# RIGHT_AR0234.net
KiCad netlist of a schematic drawn in Altium Designer
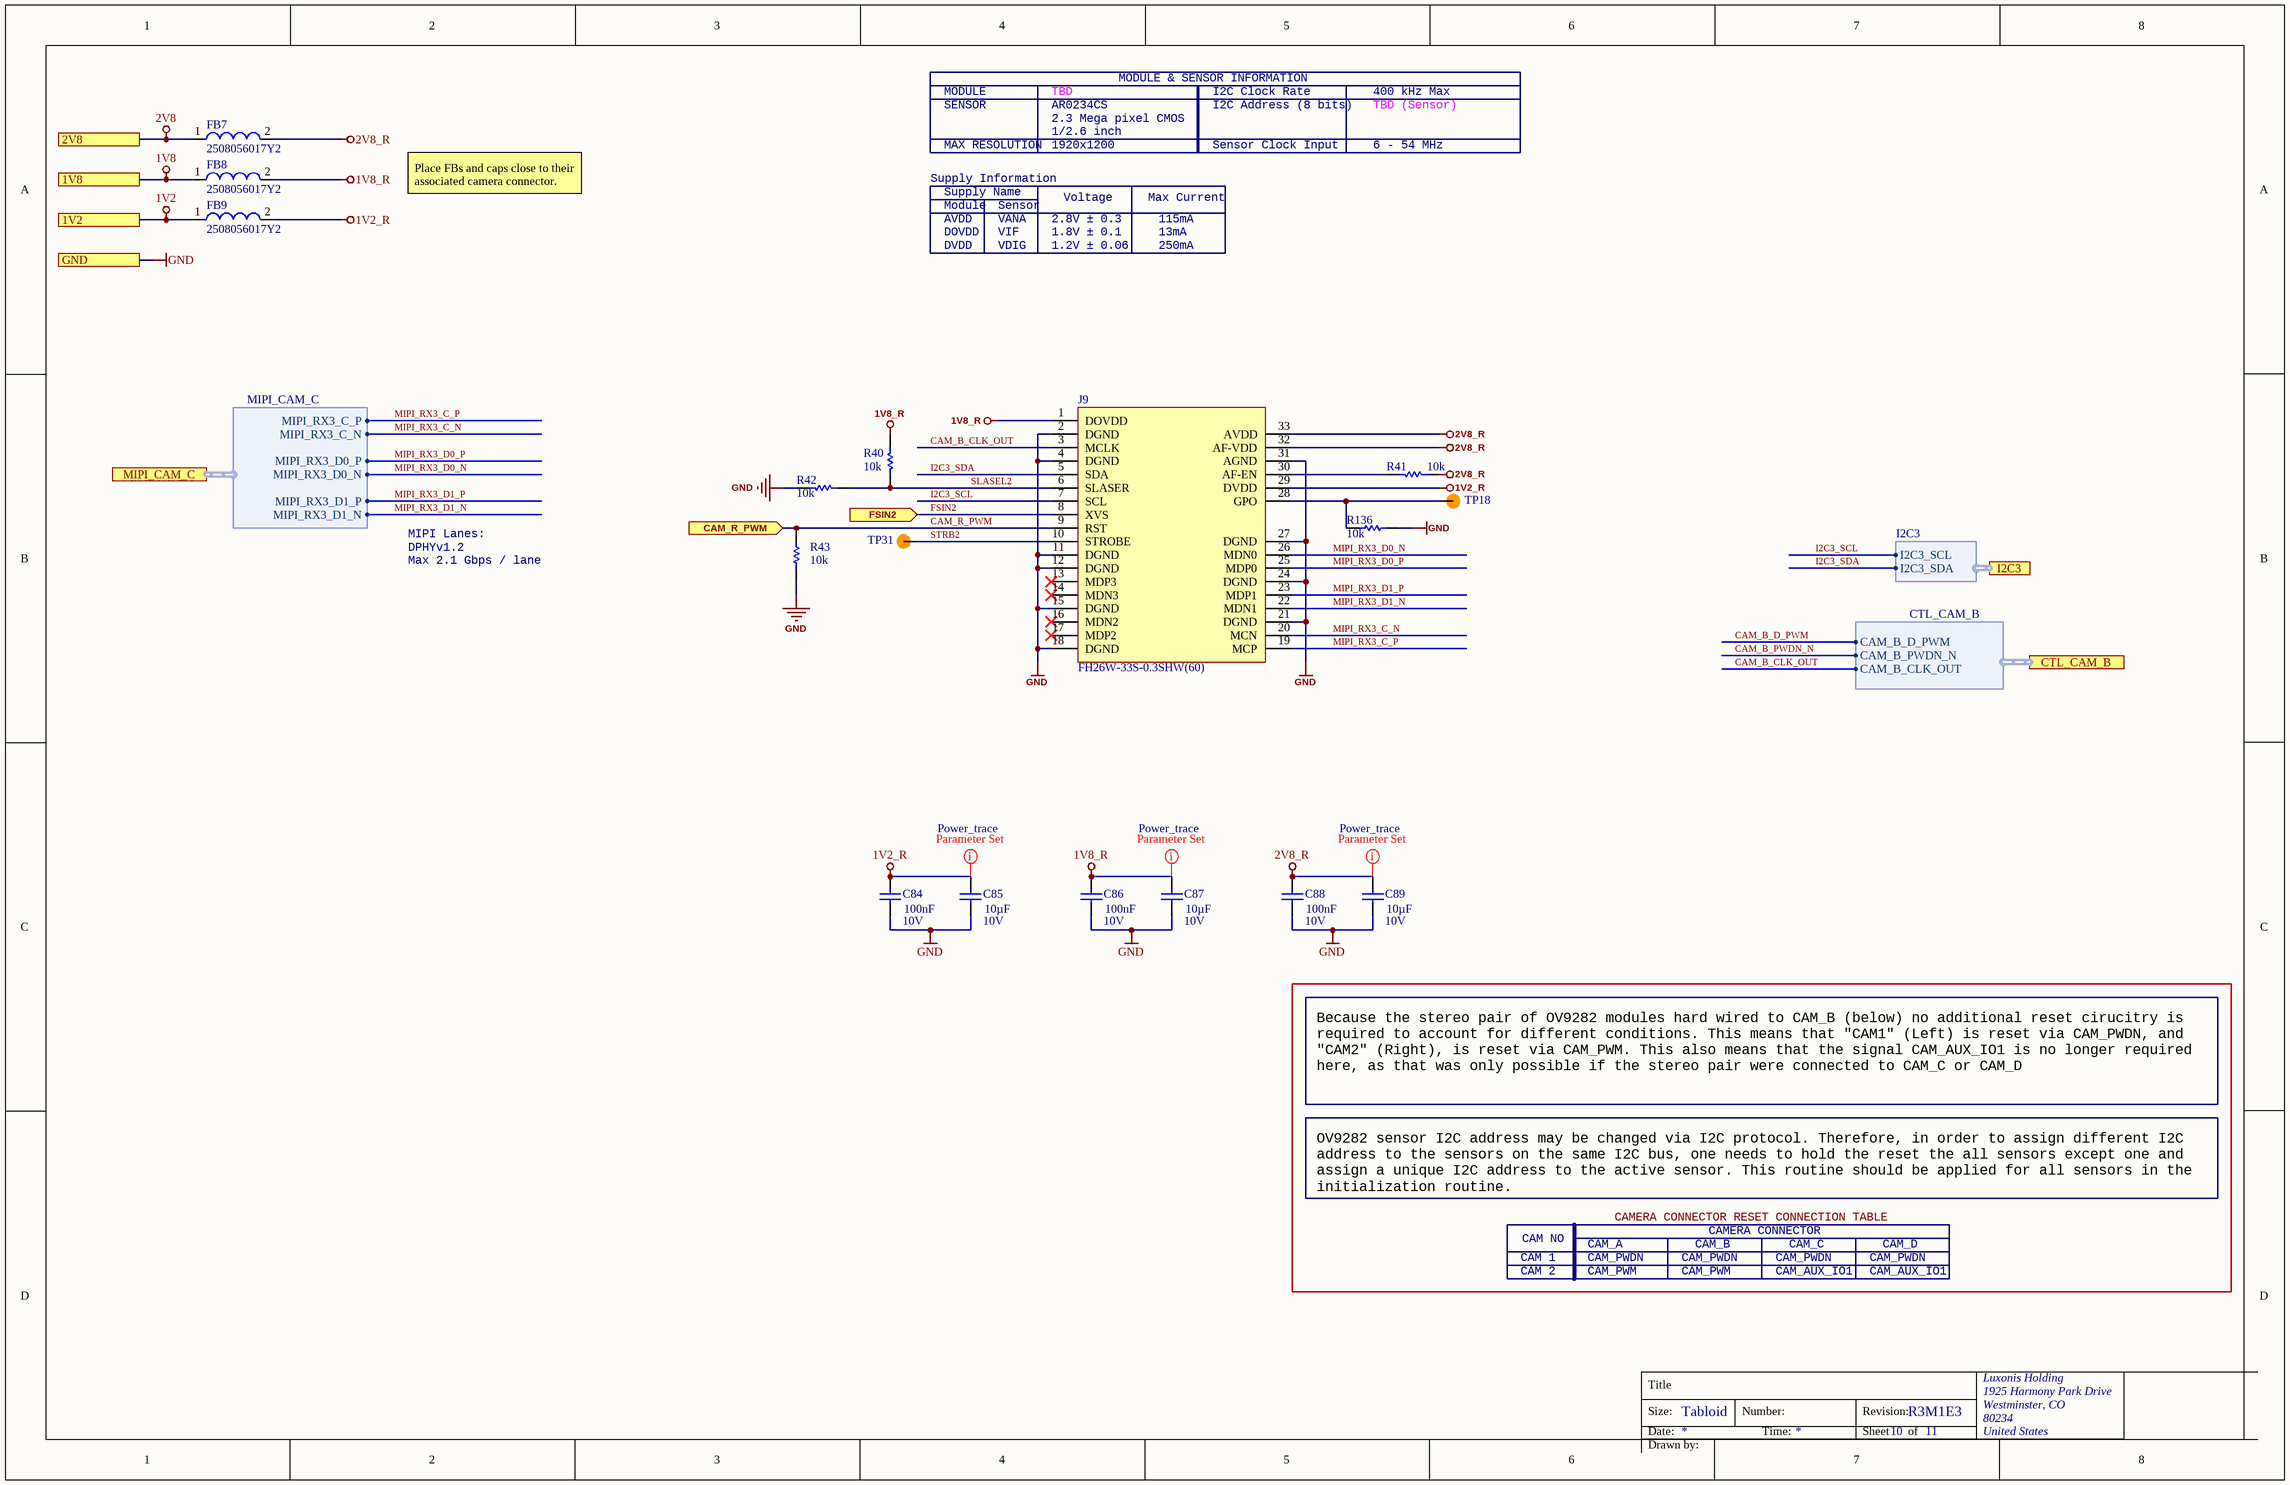
[diagram p0: RIGHT_AR0234.SchDoc]

(export (version "E")
  (design (tool "Eeschema 10.0.6"))
  (components
    (comp (ref "C84")
      (value "100nF")
      (footprint "CAPC0402(1005)70_L")
      (description "CAP CER 0.1UF 10V X7R 0402 5%")
      (fields
        (field (name "TOLERANCE") "5%")
        (field (name "VOLTAGE RATING") "10V")
        (field (name "Comment") "GRM155R71A104JA01D")
      )
      (libsource (lib "Luxonis LLC") (part "GRM188R61C475KAAJD"))
    )
    (comp (ref "C85")
      (value "10µF")
      (footprint "CAPC0603(1608)100_L")
      (description "CAP CER 10UF 10V X5R 0603 20%")
      (fields
        (field (name "TOLERANCE") "20%")
        (field (name "VOLTAGE RATING") "10V")
        (field (name "Comment") "GRM188R61A106ME69D")
      )
      (libsource (lib "Luxonis LLC") (part "LLL153C70G474ME17E"))
    )
    (comp (ref "C86")
      (value "100nF")
      (footprint "CAPC0402(1005)70_L")
      (description "CAP CER 0.1UF 10V X7R 0402 5%")
      (fields
        (field (name "TOLERANCE") "5%")
        (field (name "VOLTAGE RATING") "10V")
        (field (name "Comment") "GRM155R71A104JA01D")
      )
      (libsource (lib "Luxonis LLC") (part "GRM188R61C475KAAJD"))
    )
    (comp (ref "C87")
      (value "10µF")
      (footprint "CAPC0603(1608)100_L")
      (description "CAP CER 10UF 10V X5R 0603 20%")
      (fields
        (field (name "TOLERANCE") "20%")
        (field (name "VOLTAGE RATING") "10V")
        (field (name "Comment") "GRM188R61A106ME69D")
      )
      (libsource (lib "Luxonis LLC") (part "LLL153C70G474ME17E"))
    )
    (comp (ref "C88")
      (value "100nF")
      (footprint "CAPC0402(1005)70_L")
      (description "CAP CER 0.1UF 10V X7R 0402 5%")
      (fields
        (field (name "TOLERANCE") "5%")
        (field (name "VOLTAGE RATING") "10V")
        (field (name "Comment") "GRM155R71A104JA01D")
      )
      (libsource (lib "Luxonis LLC") (part "GRM188R61C475KAAJD"))
    )
    (comp (ref "C89")
      (value "10µF")
      (footprint "CAPC0603(1608)100_L")
      (description "CAP CER 10UF 10V X5R 0603 20%")
      (fields
        (field (name "TOLERANCE") "20%")
        (field (name "VOLTAGE RATING") "10V")
        (field (name "Comment") "GRM188R61A106ME69D")
      )
      (libsource (lib "Luxonis LLC") (part "LLL153C70G474ME17E"))
    )
    (comp (ref "FB7")
      (value "2508056017Y2")
      (footprint "2508056017Y2")
      (description "FERRITE BEAD, 0.1OHM, 2A, 0805, 600R/100MHz")
      (fields (field (name "TOLERANCE") "25%"))
      (libsource (lib "Luxonis LLC") (part "2508056017Y2"))
    )
    (comp (ref "FB8")
      (value "2508056017Y2")
      (footprint "2508056017Y2")
      (description "FERRITE BEAD, 0.1OHM, 2A, 0805, 600R/100MHz")
      (fields (field (name "TOLERANCE") "25%"))
      (libsource (lib "Luxonis LLC") (part "2508056017Y2"))
    )
    (comp (ref "FB9")
      (value "2508056017Y2")
      (footprint "2508056017Y2")
      (description "FERRITE BEAD, 0.1OHM, 2A, 0805, 600R/100MHz")
      (fields (field (name "TOLERANCE") "25%"))
      (libsource (lib "Luxonis LLC") (part "2508056017Y2"))
    )
    (comp (ref "J9")
      (value "FH26W-33S-0.3SHW(60)")
      (footprint "FH26W-33S-0.3SHW(60)")
      (description "FFC/FPC Connector, 33 Contact(s), 1 Row(s), Female, Right Angle, Surface Mount Terminal")
      (libsource (lib "Luxonis LLC") (part "FH26W-33S-0.3SHW(60)"))
    )
    (comp (ref "R40")
      (value "10k")
      (footprint "RESC0402(1005)_L")
      (description "RES SMD 10K OHM 1% 1/16W 0402")
      (fields (field (name "TOLERANCE") "1%") (field (name "Comment") "RC0402FR-1310KL"))
      (libsource (lib "Luxonis LLC") (part "RC0402FR-0722RL_1"))
    )
    (comp (ref "R41")
      (value "10k")
      (footprint "RESC0402(1005)_L")
      (description "RES SMD 10K OHM 1% 1/16W 0402")
      (fields (field (name "TOLERANCE") "1%") (field (name "Comment") "RC0402FR-1310KL"))
      (libsource (lib "Luxonis LLC") (part "RC0402FR-0722RL_1"))
    )
    (comp (ref "R42")
      (value "10k")
      (footprint "RESC0402(1005)_L")
      (description "RES SMD 10K OHM 1% 1/16W 0402")
      (fields (field (name "TOLERANCE") "1%") (field (name "Comment") "RC0402FR-1310KL"))
      (libsource (lib "Luxonis LLC") (part "RC0402FR-0722RL_1"))
    )
    (comp (ref "R43")
      (value "10k")
      (footprint "RESC0402(1005)_L")
      (description "RES SMD 10K OHM 1% 1/16W 0402")
      (fields (field (name "TOLERANCE") "1%") (field (name "Comment") "RC0402FR-1310KL"))
      (libsource (lib "Luxonis LLC") (part "RC0402FR-0722RL_1"))
    )
    (comp (ref "R136")
      (value "10k")
      (footprint "RESC0402(1005)_L")
      (description "RES SMD 10K OHM 1% 1/16W 0402")
      (fields (field (name "TOLERANCE") "1%") (field (name "Comment") "RC0402FR-1310KL"))
      (libsource (lib "Luxonis LLC") (part "RC0402FR-0722RL_1"))
    )
    (comp (ref "TP18")
      (value "TEST_POINT")
      (footprint "TP100_200_NS")
      (libsource (lib "Luxonis LLC") (part "TEST_POINT"))
    )
    (comp (ref "TP31")
      (value "TEST_POINT")
      (footprint "TP100_200_NS")
      (libsource (lib "Luxonis LLC") (part "TEST_POINT"))
    )
  )
  (nets
    (net (code "4") (name "/CAM_B_CLK_OUT") (class "Default")
      (node (ref "J9") (pin "3") (pinfunction "MCLK_3") (pintype "passive"))
    )
    (net (code "7") (name "/CAM_R_PWM") (class "Default")
      (node (ref "J9") (pin "9") (pinfunction "RST_9") (pintype "passive"))
      (node (ref "R43") (pin "2") (pinfunction "2_2") (pintype "passive"))
    )
    (net (code "8") (name "/FSIN2") (class "Default")
      (node (ref "J9") (pin "8") (pinfunction "XVS_8") (pintype "passive"))
    )
    (net (code "9") (name "/I2C3_SCL") (class "Default")
      (node (ref "J9") (pin "7") (pinfunction "SCL_7") (pintype "passive"))
    )
    (net (code "10") (name "/I2C3_SDA") (class "Default")
      (node (ref "J9") (pin "5") (pinfunction "SDA_5") (pintype "passive"))
    )
    (net (code "11") (name "/MIPI_RX3_C_N") (class "Default")
      (node (ref "J9") (pin "20") (pinfunction "MCN_20") (pintype "passive"))
    )
    (net (code "12") (name "/MIPI_RX3_C_P") (class "Default")
      (node (ref "J9") (pin "19") (pinfunction "MCP_19") (pintype "passive"))
    )
    (net (code "13") (name "/MIPI_RX3_D0_N") (class "Default")
      (node (ref "J9") (pin "26") (pinfunction "MDN0_26") (pintype "passive"))
    )
    (net (code "14") (name "/MIPI_RX3_D0_P") (class "Default")
      (node (ref "J9") (pin "25") (pinfunction "MDP0_25") (pintype "passive"))
    )
    (net (code "15") (name "/MIPI_RX3_D1_N") (class "Default")
      (node (ref "J9") (pin "22") (pinfunction "MDN1_22") (pintype "passive"))
    )
    (net (code "16") (name "/MIPI_RX3_D1_P") (class "Default")
      (node (ref "J9") (pin "23") (pinfunction "MDP1_23") (pintype "passive"))
    )
    (net (code "17") (name "/SLASEL2") (class "Default")
      (node (ref "J9") (pin "6") (pinfunction "SLASER_6") (pintype "passive"))
      (node (ref "R40") (pin "2") (pinfunction "2_2") (pintype "passive"))
      (node (ref "R42") (pin "2") (pinfunction "2_2") (pintype "passive"))
    )
    (net (code "18") (name "/STRB2") (class "Default")
      (node (ref "J9") (pin "10") (pinfunction "STROBE_10") (pintype "passive"))
      (node (ref "TP31") (pin "1") (pintype "passive"))
    )
    (net (code "22") (name "1V2") (class "Default")
      (node (ref "FB9") (pin "1") (pinfunction "1_1") (pintype "passive"))
    )
    (net (code "23") (name "1V2_R") (class "Default")
      (node (ref "C84") (pin "2") (pinfunction "2_2") (pintype "passive"))
      (node (ref "C85") (pin "2") (pinfunction "2_2") (pintype "passive"))
      (node (ref "FB9") (pin "2") (pinfunction "2_2") (pintype "passive"))
      (node (ref "J9") (pin "29") (pinfunction "DVDD_29") (pintype "passive"))
    )
    (net (code "24") (name "1V8") (class "Default")
      (node (ref "FB8") (pin "1") (pinfunction "1_1") (pintype "passive"))
    )
    (net (code "25") (name "1V8_R") (class "Default")
      (node (ref "C86") (pin "2") (pinfunction "2_2") (pintype "passive"))
      (node (ref "C87") (pin "2") (pinfunction "2_2") (pintype "passive"))
      (node (ref "FB8") (pin "2") (pinfunction "2_2") (pintype "passive"))
      (node (ref "J9") (pin "1") (pinfunction "DOVDD_1") (pintype "passive"))
      (node (ref "R40") (pin "1") (pinfunction "1_1") (pintype "passive"))
    )
    (net (code "26") (name "2V8") (class "Default")
      (node (ref "FB7") (pin "1") (pinfunction "1_1") (pintype "passive"))
    )
    (net (code "27") (name "2V8_R") (class "Default")
      (node (ref "C88") (pin "2") (pinfunction "2_2") (pintype "passive"))
      (node (ref "C89") (pin "2") (pinfunction "2_2") (pintype "passive"))
      (node (ref "FB7") (pin "2") (pinfunction "2_2") (pintype "passive"))
      (node (ref "J9") (pin "32") (pinfunction "AF-VDD_32") (pintype "passive"))
      (node (ref "J9") (pin "33") (pinfunction "AVDD_33") (pintype "passive"))
      (node (ref "R41") (pin "2") (pinfunction "2_2") (pintype "passive"))
    )
    (net (code "28") (name "GND") (class "Default")
      (node (ref "C84") (pin "1") (pinfunction "1_1") (pintype "passive"))
      (node (ref "C85") (pin "1") (pinfunction "1_1") (pintype "passive"))
      (node (ref "C86") (pin "1") (pinfunction "1_1") (pintype "passive"))
      (node (ref "C87") (pin "1") (pinfunction "1_1") (pintype "passive"))
      (node (ref "C88") (pin "1") (pinfunction "1_1") (pintype "passive"))
      (node (ref "C89") (pin "1") (pinfunction "1_1") (pintype "passive"))
      (node (ref "J9") (pin "11") (pinfunction "DGND_11") (pintype "passive"))
      (node (ref "J9") (pin "12") (pinfunction "DGND_12") (pintype "passive"))
      (node (ref "J9") (pin "15") (pinfunction "DGND_15") (pintype "passive"))
      (node (ref "J9") (pin "18") (pinfunction "DGND_18") (pintype "passive"))
      (node (ref "J9") (pin "2") (pinfunction "DGND_2") (pintype "passive"))
      (node (ref "J9") (pin "21") (pinfunction "DGND_21") (pintype "passive"))
      (node (ref "J9") (pin "24") (pinfunction "DGND_24") (pintype "passive"))
      (node (ref "J9") (pin "27") (pinfunction "DGND_27") (pintype "passive"))
      (node (ref "J9") (pin "31") (pinfunction "AGND_31") (pintype "passive"))
      (node (ref "J9") (pin "4") (pinfunction "DGND_4") (pintype "passive"))
      (node (ref "R136") (pin "2") (pinfunction "2_2") (pintype "passive"))
      (node (ref "R42") (pin "1") (pinfunction "1_1") (pintype "passive"))
      (node (ref "R43") (pin "1") (pinfunction "1_1") (pintype "passive"))
    )
    (net (code "29") (name "Net-(J9-AF-EN)") (class "Default")
      (node (ref "J9") (pin "30") (pinfunction "AF-EN_30") (pintype "passive"))
      (node (ref "R41") (pin "1") (pinfunction "1_1") (pintype "passive"))
    )
    (net (code "30") (name "Net-(J9-GPO)") (class "Default")
      (node (ref "J9") (pin "28") (pinfunction "GPO_28") (pintype "passive"))
      (node (ref "R136") (pin "1") (pinfunction "1_1") (pintype "passive"))
      (node (ref "TP18") (pin "1") (pintype "passive"))
    )
    (net (code "31") (name "unconnected-(J9-MDN2-Pad16)") (class "Default")
      (node (ref "J9") (pin "16") (pinfunction "MDN2_16") (pintype "passive+no_connect"))
    )
    (net (code "32") (name "unconnected-(J9-MDN3-Pad14)") (class "Default")
      (node (ref "J9") (pin "14") (pinfunction "MDN3_14") (pintype "passive+no_connect"))
    )
    (net (code "33") (name "unconnected-(J9-MDP2-Pad17)") (class "Default")
      (node (ref "J9") (pin "17") (pinfunction "MDP2_17") (pintype "passive+no_connect"))
    )
    (net (code "34") (name "unconnected-(J9-MDP3-Pad13)") (class "Default")
      (node (ref "J9") (pin "13") (pinfunction "MDP3_13") (pintype "passive+no_connect"))
    )
  )
)
